# FPGA_POWER_2.net
KiCad netlist of a schematic drawn in Altium Designer
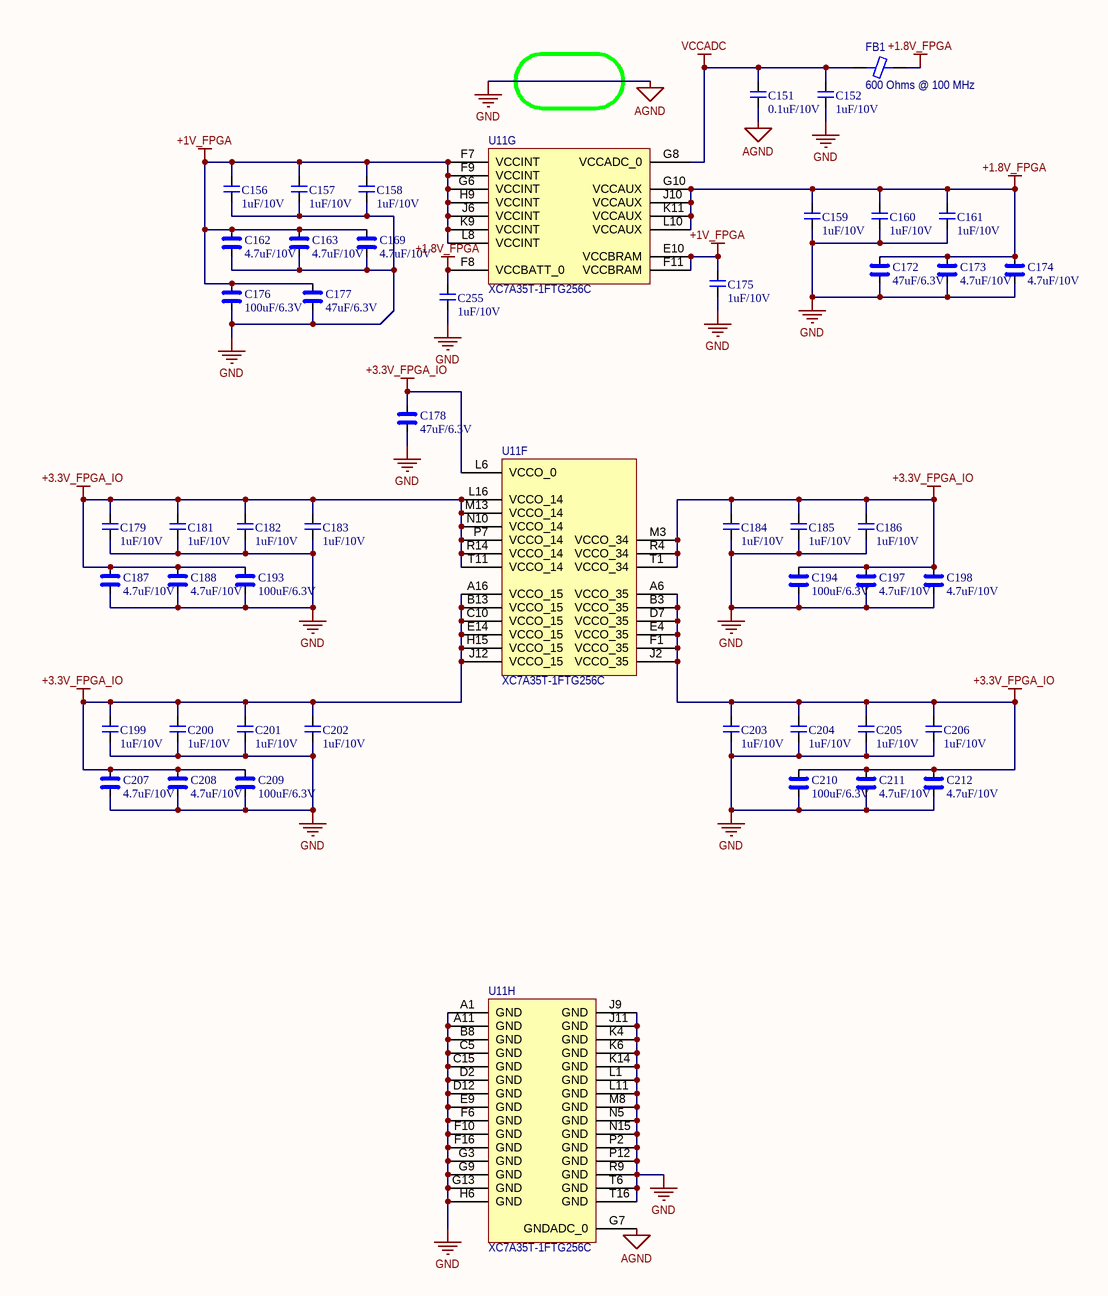
[diagram p0: FPGA_POWER_2.SchDoc]

(export (version "E")
  (design (tool "Eeschema 10.0.6"))
  (components
    (comp (ref "C151")
      (value "0.1uF/10V")
      (footprint "CAP_C_1005X50_L")
      (description "CAP")
      (libsource (lib "LABLIB") (part "_CAP_C_2"))
    )
    (comp (ref "C152")
      (value "1uF/10V")
      (footprint "CAP_C_1005X50_L")
      (description "CAP")
      (libsource (lib "LABLIB") (part "_CAP_C_2"))
    )
    (comp (ref "C156")
      (value "1uF/10V")
      (footprint "CAP_C_1005X50_L")
      (description "CAP")
      (libsource (lib "LABLIB") (part "_CAP_C_2"))
    )
    (comp (ref "C157")
      (value "1uF/10V")
      (footprint "CAP_C_1005X50_L")
      (description "CAP")
      (libsource (lib "LABLIB") (part "_CAP_C_2"))
    )
    (comp (ref "C158")
      (value "1uF/10V")
      (footprint "CAP_C_1005X50_L")
      (description "CAP")
      (libsource (lib "LABLIB") (part "_CAP_C_2"))
    )
    (comp (ref "C159")
      (value "1uF/10V")
      (footprint "CAP_C_1005X50_L")
      (description "CAP")
      (libsource (lib "LABLIB") (part "_CAP_C_2"))
    )
    (comp (ref "C160")
      (value "1uF/10V")
      (footprint "CAP_C_1005X50_L")
      (description "CAP")
      (libsource (lib "LABLIB") (part "_CAP_C_2"))
    )
    (comp (ref "C161")
      (value "1uF/10V")
      (footprint "CAP_C_1005X50_L")
      (description "CAP")
      (libsource (lib "LABLIB") (part "_CAP_C_2"))
    )
    (comp (ref "C162")
      (value "4.7uF/10V")
      (footprint "CAP_C_1005X50_L")
      (description "CAP")
      (libsource (lib "LABLIB") (part "_CAP_C_High_2"))
    )
    (comp (ref "C163")
      (value "4.7uF/10V")
      (footprint "CAP_C_1005X50_L")
      (description "CAP")
      (libsource (lib "LABLIB") (part "_CAP_C_High_2"))
    )
    (comp (ref "C169")
      (value "4.7uF/10V")
      (footprint "CAP_C_1005X50_L")
      (description "CAP")
      (libsource (lib "LABLIB") (part "_CAP_C_High_2"))
    )
    (comp (ref "C172")
      (value "47uF/6.3V")
      (footprint "CAP_C_1608X80")
      (description "CAP")
      (libsource (lib "LABLIB") (part "_CAP_C_High_2"))
    )
    (comp (ref "C173")
      (value "4.7uF/10V")
      (footprint "CAP_C_1005X50_L")
      (description "CAP")
      (libsource (lib "LABLIB") (part "_CAP_C_High_2"))
    )
    (comp (ref "C174")
      (value "4.7uF/10V")
      (footprint "CAP_C_1005X50_L")
      (description "CAP")
      (libsource (lib "LABLIB") (part "_CAP_C_High_2"))
    )
    (comp (ref "C175")
      (value "1uF/10V")
      (footprint "CAP_C_1005X50_L")
      (description "CAP")
      (libsource (lib "LABLIB") (part "_CAP_C_2"))
    )
    (comp (ref "C176")
      (value "100uF/6.3V")
      (footprint "CAP_C_2012X110")
      (description "CAP")
      (libsource (lib "LABLIB") (part "_CAP_C_High_2"))
    )
    (comp (ref "C177")
      (value "47uF/6.3V")
      (footprint "CAP_C_1608X80")
      (description "CAP")
      (libsource (lib "LABLIB") (part "_CAP_C_High_2"))
    )
    (comp (ref "C178")
      (value "47uF/6.3V")
      (footprint "CAP_C_1608X80")
      (description "CAP")
      (libsource (lib "LABLIB") (part "_CAP_C_High_2"))
    )
    (comp (ref "C179")
      (value "1uF/10V")
      (footprint "CAP_C_1005X50_L")
      (description "CAP")
      (libsource (lib "LABLIB") (part "_CAP_C_2"))
    )
    (comp (ref "C181")
      (value "1uF/10V")
      (footprint "CAP_C_1005X50_L")
      (description "CAP")
      (libsource (lib "LABLIB") (part "_CAP_C_2"))
    )
    (comp (ref "C182")
      (value "1uF/10V")
      (footprint "CAP_C_1005X50_L")
      (description "CAP")
      (libsource (lib "LABLIB") (part "_CAP_C_2"))
    )
    (comp (ref "C183")
      (value "1uF/10V")
      (footprint "CAP_C_1005X50_L")
      (description "CAP")
      (libsource (lib "LABLIB") (part "_CAP_C_2"))
    )
    (comp (ref "C184")
      (value "1uF/10V")
      (footprint "CAP_C_1005X50_L")
      (description "CAP")
      (libsource (lib "LABLIB") (part "_CAP_C_2"))
    )
    (comp (ref "C185")
      (value "1uF/10V")
      (footprint "CAP_C_1005X50_L")
      (description "CAP")
      (libsource (lib "LABLIB") (part "_CAP_C_2"))
    )
    (comp (ref "C186")
      (value "1uF/10V")
      (footprint "CAP_C_1005X50_L")
      (description "CAP")
      (libsource (lib "LABLIB") (part "_CAP_C_2"))
    )
    (comp (ref "C187")
      (value "4.7uF/10V")
      (footprint "CAP_C_1005X50_L")
      (description "CAP")
      (libsource (lib "LABLIB") (part "_CAP_C_High_2"))
    )
    (comp (ref "C188")
      (value "4.7uF/10V")
      (footprint "CAP_C_1005X50_L")
      (description "CAP")
      (libsource (lib "LABLIB") (part "_CAP_C_High_2"))
    )
    (comp (ref "C193")
      (value "100uF/6.3V")
      (footprint "CAP_C_2012X110")
      (description "CAP")
      (libsource (lib "LABLIB") (part "_CAP_C_High_2"))
    )
    (comp (ref "C194")
      (value "100uF/6.3V")
      (footprint "CAP_C_2012X110")
      (description "CAP")
      (libsource (lib "LABLIB") (part "_CAP_C_High_2"))
    )
    (comp (ref "C197")
      (value "4.7uF/10V")
      (footprint "CAP_C_1005X50_L")
      (description "CAP")
      (libsource (lib "LABLIB") (part "_CAP_C_High_2"))
    )
    (comp (ref "C198")
      (value "4.7uF/10V")
      (footprint "CAP_C_1005X50_L")
      (description "CAP")
      (libsource (lib "LABLIB") (part "_CAP_C_High_2"))
    )
    (comp (ref "C199")
      (value "1uF/10V")
      (footprint "CAP_C_1005X50_L")
      (description "CAP")
      (libsource (lib "LABLIB") (part "_CAP_C_2"))
    )
    (comp (ref "C200")
      (value "1uF/10V")
      (footprint "CAP_C_1005X50_L")
      (description "CAP")
      (libsource (lib "LABLIB") (part "_CAP_C_2"))
    )
    (comp (ref "C201")
      (value "1uF/10V")
      (footprint "CAP_C_1005X50_L")
      (description "CAP")
      (libsource (lib "LABLIB") (part "_CAP_C_2"))
    )
    (comp (ref "C202")
      (value "1uF/10V")
      (footprint "CAP_C_1005X50_L")
      (description "CAP")
      (libsource (lib "LABLIB") (part "_CAP_C_2"))
    )
    (comp (ref "C203")
      (value "1uF/10V")
      (footprint "CAP_C_1005X50_L")
      (description "CAP")
      (libsource (lib "LABLIB") (part "_CAP_C_2"))
    )
    (comp (ref "C204")
      (value "1uF/10V")
      (footprint "CAP_C_1005X50_L")
      (description "CAP")
      (libsource (lib "LABLIB") (part "_CAP_C_2"))
    )
    (comp (ref "C205")
      (value "1uF/10V")
      (footprint "CAP_C_1005X50_L")
      (description "CAP")
      (libsource (lib "LABLIB") (part "_CAP_C_2"))
    )
    (comp (ref "C206")
      (value "1uF/10V")
      (footprint "CAP_C_1005X50_L")
      (description "CAP")
      (libsource (lib "LABLIB") (part "_CAP_C_2"))
    )
    (comp (ref "C207")
      (value "4.7uF/10V")
      (footprint "CAP_C_1005X50_L")
      (description "CAP")
      (libsource (lib "LABLIB") (part "_CAP_C_High_2"))
    )
    (comp (ref "C208")
      (value "4.7uF/10V")
      (footprint "CAP_C_1005X50_L")
      (description "CAP")
      (libsource (lib "LABLIB") (part "_CAP_C_High_2"))
    )
    (comp (ref "C209")
      (value "100uF/6.3V")
      (footprint "CAP_C_2012X110")
      (description "CAP")
      (libsource (lib "LABLIB") (part "_CAP_C_High_2"))
    )
    (comp (ref "C210")
      (value "100uF/6.3V")
      (footprint "CAP_C_2012X110")
      (description "CAP")
      (libsource (lib "LABLIB") (part "_CAP_C_High_2"))
    )
    (comp (ref "C211")
      (value "4.7uF/10V")
      (footprint "CAP_C_1005X50_L")
      (description "CAP")
      (libsource (lib "LABLIB") (part "_CAP_C_High_2"))
    )
    (comp (ref "C212")
      (value "4.7uF/10V")
      (footprint "CAP_C_1005X50_L")
      (description "CAP")
      (libsource (lib "LABLIB") (part "_CAP_C_High_2"))
    )
    (comp (ref "C255")
      (value "1uF/10V")
      (footprint "CAP_C_1005X50_L")
      (description "CAP")
      (libsource (lib "LABLIB") (part "_CAP_C_2"))
    )
    (comp (ref "FB1")
      (value "600 Ohms @ 100 MHz")
      (footprint "IND_C_1608X60")
      (description "FERRITE BEAD 600 OHM 0603 1LN")
      (fields
        (field (name "PART NUMBER") "BLM18AG601SN1D")
        (field (name "MANUFACTURER") "Murata Electronics")
      )
      (libsource (lib "altium_library") (part "Ferrite Chip"))
    )
    (comp (ref "U11")
      (value "XC7A35T-1FTG256C")
      (footprint "FTG256")
      (description "Artix-7 FPGA, 170 User I/Os, 0 GTP, 256-Ball BGA, Speed Grade 1, Commercial Grade, Pb-Free")
      (fields (field (name "MANUFACTURER") "Xilinx"))
      (libsource (lib "Altium Content Vault") (part "XLNX-XC7A35T-FTG256"))
    )
  )
  (nets
    (net (code "1") (name "+1.8V_FPGA") (class "Default")
      (node (ref "C159") (pin "1") (pinfunction "1_1") (pintype "passive"))
      (node (ref "C160") (pin "1") (pinfunction "1_1") (pintype "passive"))
      (node (ref "C161") (pin "1") (pinfunction "1_1") (pintype "passive"))
      (node (ref "C172") (pin "1") (pinfunction "1_1") (pintype "passive"))
      (node (ref "C173") (pin "1") (pinfunction "1_1") (pintype "passive"))
      (node (ref "C174") (pin "1") (pinfunction "1_1") (pintype "passive"))
      (node (ref "C255") (pin "1") (pinfunction "1_1") (pintype "passive"))
      (node (ref "FB1") (pin "2") (pinfunction "2_2") (pintype "passive"))
      (node (ref "U11") (pin "F8") (pinfunction "VCCBATT_0_F8") (pintype "power_in"))
      (node (ref "U11") (pin "G10") (pinfunction "VCCAUX_G10") (pintype "power_in"))
      (node (ref "U11") (pin "J10") (pinfunction "VCCAUX_J10") (pintype "power_in"))
      (node (ref "U11") (pin "K11") (pinfunction "VCCAUX_K11") (pintype "power_in"))
      (node (ref "U11") (pin "L10") (pinfunction "VCCAUX_L10") (pintype "power_in"))
    )
    (net (code "2") (name "+1V_FPGA") (class "Default")
      (node (ref "C156") (pin "1") (pinfunction "1_1") (pintype "passive"))
      (node (ref "C157") (pin "1") (pinfunction "1_1") (pintype "passive"))
      (node (ref "C158") (pin "1") (pinfunction "1_1") (pintype "passive"))
      (node (ref "C162") (pin "1") (pinfunction "1_1") (pintype "passive"))
      (node (ref "C163") (pin "1") (pinfunction "1_1") (pintype "passive"))
      (node (ref "C169") (pin "1") (pinfunction "1_1") (pintype "passive"))
      (node (ref "C175") (pin "1") (pinfunction "1_1") (pintype "passive"))
      (node (ref "C176") (pin "1") (pinfunction "1_1") (pintype "passive"))
      (node (ref "C177") (pin "1") (pinfunction "1_1") (pintype "passive"))
      (node (ref "U11") (pin "E10") (pinfunction "VCCBRAM_E10") (pintype "power_in"))
      (node (ref "U11") (pin "F11") (pinfunction "VCCBRAM_F11") (pintype "power_in"))
      (node (ref "U11") (pin "F7") (pinfunction "VCCINT_F7") (pintype "power_in"))
      (node (ref "U11") (pin "F9") (pinfunction "VCCINT_F9") (pintype "power_in"))
      (node (ref "U11") (pin "G6") (pinfunction "VCCINT_G6") (pintype "power_in"))
      (node (ref "U11") (pin "H9") (pinfunction "VCCINT_H9") (pintype "power_in"))
      (node (ref "U11") (pin "J6") (pinfunction "VCCINT_J6") (pintype "power_in"))
      (node (ref "U11") (pin "K9") (pinfunction "VCCINT_K9") (pintype "power_in"))
      (node (ref "U11") (pin "L8") (pinfunction "VCCINT_L8") (pintype "power_in"))
    )
    (net (code "3") (name "+3.3V_FPGA_IO") (class "Default")
      (node (ref "C178") (pin "1") (pinfunction "1_1") (pintype "passive"))
      (node (ref "C179") (pin "1") (pinfunction "1_1") (pintype "passive"))
      (node (ref "C181") (pin "1") (pinfunction "1_1") (pintype "passive"))
      (node (ref "C182") (pin "1") (pinfunction "1_1") (pintype "passive"))
      (node (ref "C183") (pin "1") (pinfunction "1_1") (pintype "passive"))
      (node (ref "C184") (pin "1") (pinfunction "1_1") (pintype "passive"))
      (node (ref "C185") (pin "1") (pinfunction "1_1") (pintype "passive"))
      (node (ref "C186") (pin "1") (pinfunction "1_1") (pintype "passive"))
      (node (ref "C187") (pin "1") (pinfunction "1_1") (pintype "passive"))
      (node (ref "C188") (pin "1") (pinfunction "1_1") (pintype "passive"))
      (node (ref "C193") (pin "1") (pinfunction "1_1") (pintype "passive"))
      (node (ref "C194") (pin "1") (pinfunction "1_1") (pintype "passive"))
      (node (ref "C197") (pin "1") (pinfunction "1_1") (pintype "passive"))
      (node (ref "C198") (pin "1") (pinfunction "1_1") (pintype "passive"))
      (node (ref "C199") (pin "1") (pinfunction "1_1") (pintype "passive"))
      (node (ref "C200") (pin "1") (pinfunction "1_1") (pintype "passive"))
      (node (ref "C201") (pin "1") (pinfunction "1_1") (pintype "passive"))
      (node (ref "C202") (pin "1") (pinfunction "1_1") (pintype "passive"))
      (node (ref "C203") (pin "1") (pinfunction "1_1") (pintype "passive"))
      (node (ref "C204") (pin "1") (pinfunction "1_1") (pintype "passive"))
      (node (ref "C205") (pin "1") (pinfunction "1_1") (pintype "passive"))
      (node (ref "C206") (pin "1") (pinfunction "1_1") (pintype "passive"))
      (node (ref "C207") (pin "1") (pinfunction "1_1") (pintype "passive"))
      (node (ref "C208") (pin "1") (pinfunction "1_1") (pintype "passive"))
      (node (ref "C209") (pin "1") (pinfunction "1_1") (pintype "passive"))
      (node (ref "C210") (pin "1") (pinfunction "1_1") (pintype "passive"))
      (node (ref "C211") (pin "1") (pinfunction "1_1") (pintype "passive"))
      (node (ref "C212") (pin "1") (pinfunction "1_1") (pintype "passive"))
      (node (ref "U11") (pin "A16") (pinfunction "VCCO_15_A16") (pintype "power_in"))
      (node (ref "U11") (pin "A6") (pinfunction "VCCO_35_A6") (pintype "power_in"))
      (node (ref "U11") (pin "B13") (pinfunction "VCCO_15_B13") (pintype "power_in"))
      (node (ref "U11") (pin "B3") (pinfunction "VCCO_35_B3") (pintype "power_in"))
      (node (ref "U11") (pin "C10") (pinfunction "VCCO_15_C10") (pintype "power_in"))
      (node (ref "U11") (pin "D7") (pinfunction "VCCO_35_D7") (pintype "power_in"))
      (node (ref "U11") (pin "E14") (pinfunction "VCCO_15_E14") (pintype "power_in"))
      (node (ref "U11") (pin "E4") (pinfunction "VCCO_35_E4") (pintype "power_in"))
      (node (ref "U11") (pin "F1") (pinfunction "VCCO_35_F1") (pintype "power_in"))
      (node (ref "U11") (pin "H15") (pinfunction "VCCO_15_H15") (pintype "power_in"))
      (node (ref "U11") (pin "J12") (pinfunction "VCCO_15_J12") (pintype "power_in"))
      (node (ref "U11") (pin "J2") (pinfunction "VCCO_35_J2") (pintype "power_in"))
      (node (ref "U11") (pin "L16") (pinfunction "VCCO_14_L16") (pintype "power_in"))
      (node (ref "U11") (pin "L6") (pinfunction "VCCO_0_L6") (pintype "power_in"))
      (node (ref "U11") (pin "M13") (pinfunction "VCCO_14_M13") (pintype "power_in"))
      (node (ref "U11") (pin "M3") (pinfunction "VCCO_34_M3") (pintype "power_in"))
      (node (ref "U11") (pin "N10") (pinfunction "VCCO_14_N10") (pintype "power_in"))
      (node (ref "U11") (pin "P7") (pinfunction "VCCO_14_P7") (pintype "power_in"))
      (node (ref "U11") (pin "R14") (pinfunction "VCCO_14_R14") (pintype "power_in"))
      (node (ref "U11") (pin "R4") (pinfunction "VCCO_34_R4") (pintype "power_in"))
      (node (ref "U11") (pin "T1") (pinfunction "VCCO_34_T1") (pintype "power_in"))
      (node (ref "U11") (pin "T11") (pinfunction "VCCO_14_T11") (pintype "power_in"))
    )
    (net (code "4") (name "AGND") (class "Default")
      (node (ref "C151") (pin "2") (pinfunction "2_2") (pintype "passive"))
      (node (ref "C152") (pin "2") (pinfunction "2_2") (pintype "passive"))
      (node (ref "C156") (pin "2") (pinfunction "2_2") (pintype "passive"))
      (node (ref "C157") (pin "2") (pinfunction "2_2") (pintype "passive"))
      (node (ref "C158") (pin "2") (pinfunction "2_2") (pintype "passive"))
      (node (ref "C159") (pin "2") (pinfunction "2_2") (pintype "passive"))
      (node (ref "C160") (pin "2") (pinfunction "2_2") (pintype "passive"))
      (node (ref "C161") (pin "2") (pinfunction "2_2") (pintype "passive"))
      (node (ref "C162") (pin "2") (pinfunction "2_2") (pintype "passive"))
      (node (ref "C163") (pin "2") (pinfunction "2_2") (pintype "passive"))
      (node (ref "C169") (pin "2") (pinfunction "2_2") (pintype "passive"))
      (node (ref "C172") (pin "2") (pinfunction "2_2") (pintype "passive"))
      (node (ref "C173") (pin "2") (pinfunction "2_2") (pintype "passive"))
      (node (ref "C174") (pin "2") (pinfunction "2_2") (pintype "passive"))
      (node (ref "C175") (pin "2") (pinfunction "2_2") (pintype "passive"))
      (node (ref "C176") (pin "2") (pinfunction "2_2") (pintype "passive"))
      (node (ref "C177") (pin "2") (pinfunction "2_2") (pintype "passive"))
      (node (ref "C178") (pin "2") (pinfunction "2_2") (pintype "passive"))
      (node (ref "C179") (pin "2") (pinfunction "2_2") (pintype "passive"))
      (node (ref "C181") (pin "2") (pinfunction "2_2") (pintype "passive"))
      (node (ref "C182") (pin "2") (pinfunction "2_2") (pintype "passive"))
      (node (ref "C183") (pin "2") (pinfunction "2_2") (pintype "passive"))
      (node (ref "C184") (pin "2") (pinfunction "2_2") (pintype "passive"))
      (node (ref "C185") (pin "2") (pinfunction "2_2") (pintype "passive"))
      (node (ref "C186") (pin "2") (pinfunction "2_2") (pintype "passive"))
      (node (ref "C187") (pin "2") (pinfunction "2_2") (pintype "passive"))
      (node (ref "C188") (pin "2") (pinfunction "2_2") (pintype "passive"))
      (node (ref "C193") (pin "2") (pinfunction "2_2") (pintype "passive"))
      (node (ref "C194") (pin "2") (pinfunction "2_2") (pintype "passive"))
      (node (ref "C197") (pin "2") (pinfunction "2_2") (pintype "passive"))
      (node (ref "C198") (pin "2") (pinfunction "2_2") (pintype "passive"))
      (node (ref "C199") (pin "2") (pinfunction "2_2") (pintype "passive"))
      (node (ref "C200") (pin "2") (pinfunction "2_2") (pintype "passive"))
      (node (ref "C201") (pin "2") (pinfunction "2_2") (pintype "passive"))
      (node (ref "C202") (pin "2") (pinfunction "2_2") (pintype "passive"))
      (node (ref "C203") (pin "2") (pinfunction "2_2") (pintype "passive"))
      (node (ref "C204") (pin "2") (pinfunction "2_2") (pintype "passive"))
      (node (ref "C205") (pin "2") (pinfunction "2_2") (pintype "passive"))
      (node (ref "C206") (pin "2") (pinfunction "2_2") (pintype "passive"))
      (node (ref "C207") (pin "2") (pinfunction "2_2") (pintype "passive"))
      (node (ref "C208") (pin "2") (pinfunction "2_2") (pintype "passive"))
      (node (ref "C209") (pin "2") (pinfunction "2_2") (pintype "passive"))
      (node (ref "C210") (pin "2") (pinfunction "2_2") (pintype "passive"))
      (node (ref "C211") (pin "2") (pinfunction "2_2") (pintype "passive"))
      (node (ref "C212") (pin "2") (pinfunction "2_2") (pintype "passive"))
      (node (ref "C255") (pin "2") (pinfunction "2_2") (pintype "passive"))
      (node (ref "U11") (pin "A1") (pinfunction "GND_A1") (pintype "power_in"))
      (node (ref "U11") (pin "A11") (pinfunction "GND_A11") (pintype "power_in"))
      (node (ref "U11") (pin "B8") (pinfunction "GND_B8") (pintype "power_in"))
      (node (ref "U11") (pin "C15") (pinfunction "GND_C15") (pintype "power_in"))
      (node (ref "U11") (pin "C5") (pinfunction "GND_C5") (pintype "power_in"))
      (node (ref "U11") (pin "D12") (pinfunction "GND_D12") (pintype "power_in"))
      (node (ref "U11") (pin "D2") (pinfunction "GND_D2") (pintype "power_in"))
      (node (ref "U11") (pin "E9") (pinfunction "GND_E9") (pintype "power_in"))
      (node (ref "U11") (pin "F10") (pinfunction "GND_F10") (pintype "power_in"))
      (node (ref "U11") (pin "F16") (pinfunction "GND_F16") (pintype "power_in"))
      (node (ref "U11") (pin "F6") (pinfunction "GND_F6") (pintype "power_in"))
      (node (ref "U11") (pin "G13") (pinfunction "GND_G13") (pintype "power_in"))
      (node (ref "U11") (pin "G3") (pinfunction "GND_G3") (pintype "power_in"))
      (node (ref "U11") (pin "G7") (pinfunction "GNDADC_0_G7") (pintype "power_in"))
      (node (ref "U11") (pin "G9") (pinfunction "GND_G9") (pintype "power_in"))
      (node (ref "U11") (pin "H6") (pinfunction "GND_H6") (pintype "power_in"))
      (node (ref "U11") (pin "J11") (pinfunction "GND_J11") (pintype "power_in"))
      (node (ref "U11") (pin "J9") (pinfunction "GND_J9") (pintype "power_in"))
      (node (ref "U11") (pin "K14") (pinfunction "GND_K14") (pintype "power_in"))
      (node (ref "U11") (pin "K4") (pinfunction "GND_K4") (pintype "power_in"))
      (node (ref "U11") (pin "K6") (pinfunction "GND_K6") (pintype "power_in"))
      (node (ref "U11") (pin "L1") (pinfunction "GND_L1") (pintype "power_in"))
      (node (ref "U11") (pin "L11") (pinfunction "GND_L11") (pintype "power_in"))
      (node (ref "U11") (pin "M8") (pinfunction "GND_M8") (pintype "power_in"))
      (node (ref "U11") (pin "N15") (pinfunction "GND_N15") (pintype "power_in"))
      (node (ref "U11") (pin "N5") (pinfunction "GND_N5") (pintype "power_in"))
      (node (ref "U11") (pin "P12") (pinfunction "GND_P12") (pintype "power_in"))
      (node (ref "U11") (pin "P2") (pinfunction "GND_P2") (pintype "power_in"))
      (node (ref "U11") (pin "R9") (pinfunction "GND_R9") (pintype "power_in"))
      (node (ref "U11") (pin "T16") (pinfunction "GND_T16") (pintype "power_in"))
      (node (ref "U11") (pin "T6") (pinfunction "GND_T6") (pintype "power_in"))
    )
    (net (code "5") (name "VCCADC") (class "Default")
      (node (ref "C151") (pin "1") (pinfunction "1_1") (pintype "passive"))
      (node (ref "C152") (pin "1") (pinfunction "1_1") (pintype "passive"))
      (node (ref "FB1") (pin "1") (pinfunction "1_1") (pintype "passive"))
      (node (ref "U11") (pin "G8") (pinfunction "VCCADC_0_G8") (pintype "power_in"))
    )
  )
)
